# facetHound_base_module_v12.net
KiCad netlist of a schematic drawn in EAGLE
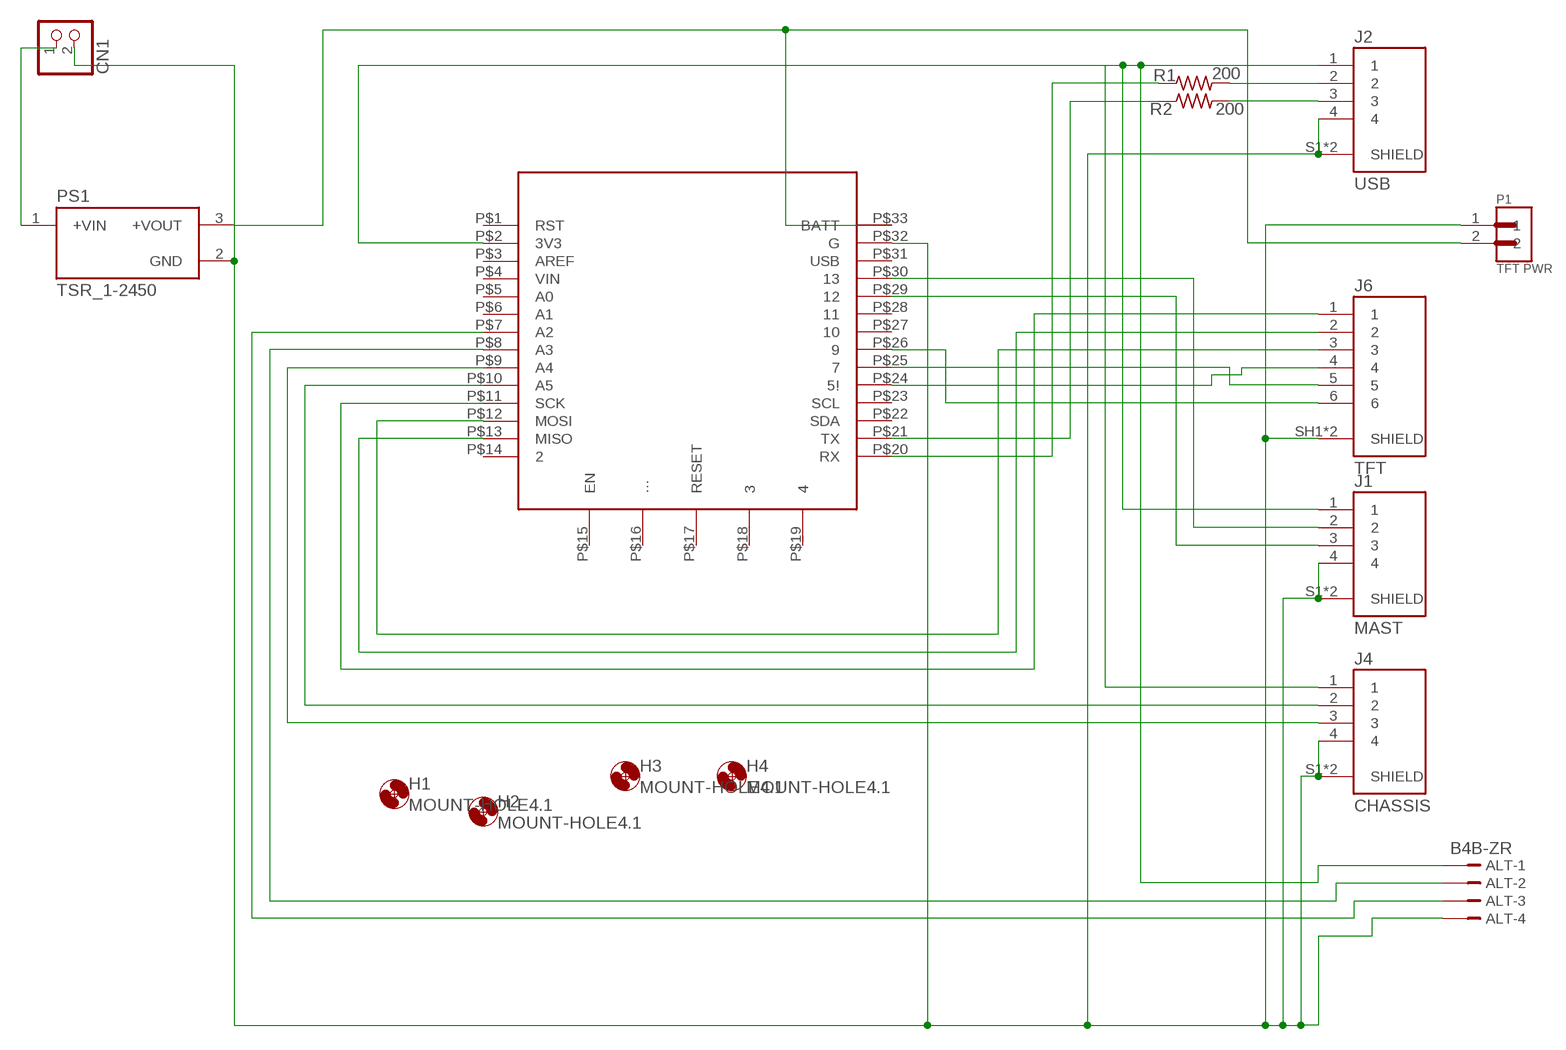
[diagram p0: schematic, sheet 1]

(export (version "E")
  (design (tool "Eeschema 10.0.6"))
  (components
    (comp (ref "ALT")
      (value "B4B-ZR")
      (footprint "eagle-import:B4B-ZR")
      (fields (field (name "MF") "FARNELL") (field (name "MPN") "B4B-ZR(LF)(SN)"))
      (libsource (lib "eagle-import") (part "?4B-ZRB"))
    )
    (comp (ref "CN1")
      (value "JST_2PIN-THM-RA")
      (footprint "eagle-import:JST-PH-2-THM-RA")
      (libsource (lib "eagle-import") (part "JST_2PIN-THM-RA"))
    )
    (comp (ref "H1")
      (value "MOUNT-HOLE4.1")
      (footprint "eagle-import:4,1")
      (libsource (lib "eagle-import") (part "MOUNT-HOLE4.1"))
    )
    (comp (ref "H2")
      (value "MOUNT-HOLE4.1")
      (footprint "eagle-import:4,1")
      (libsource (lib "eagle-import") (part "MOUNT-HOLE4.1"))
    )
    (comp (ref "H3")
      (value "MOUNT-HOLE4.1")
      (footprint "eagle-import:4,1")
      (libsource (lib "eagle-import") (part "MOUNT-HOLE4.1"))
    )
    (comp (ref "H4")
      (value "MOUNT-HOLE4.1")
      (footprint "eagle-import:4,1")
      (libsource (lib "eagle-import") (part "MOUNT-HOLE4.1"))
    )
    (comp (ref "J1")
      (value "MAST")
      (footprint "eagle-import:JST_S4B-ZR-SM4A-TF(LF)(SN)")
      (fields (field (name "MF") "JST Sales") (field (name "MP") "S4B-ZR-SM4A-TF(LF)(SN)"))
      (libsource (lib "eagle-import") (part "S4B-ZR-SM4A-TF(LF)(SN)"))
    )
    (comp (ref "J2")
      (value "USB")
      (footprint "eagle-import:JST_S4B-ZR-SM4A-TF(LF)(SN)")
      (fields (field (name "MF") "JST Sales") (field (name "MP") "S4B-ZR-SM4A-TF(LF)(SN)"))
      (libsource (lib "eagle-import") (part "S4B-ZR-SM4A-TF(LF)(SN)"))
    )
    (comp (ref "J4")
      (value "CHASSIS")
      (footprint "eagle-import:JST_S4B-ZR-SM4A-TF(LF)(SN)")
      (fields (field (name "MF") "JST Sales") (field (name "MP") "S4B-ZR-SM4A-TF(LF)(SN)"))
      (libsource (lib "eagle-import") (part "S4B-ZR-SM4A-TF(LF)(SN)"))
    )
    (comp (ref "J6")
      (value "TFT")
      (footprint "eagle-import:JST_S6B-ZR-SM4A-TF(LF)(SN)")
      (fields (field (name "MF") "JST Sales America Inc.") (field (name "MP") "S6B-ZR-SM4A-TF(LF)(SN)"))
      (libsource (lib "eagle-import") (part "S6B-ZR-SM4A-TF(LF)(SN)"))
    )
    (comp (ref "P1")
      (value "TFT PWR")
      (footprint "eagle-import:JST_S2B-ZR-SM4A-TF")
      (fields (field (name "MF") "JST Sales") (field (name "MP") "S2B-ZR-SM4A-TF"))
      (libsource (lib "eagle-import") (part "S2B-ZR-SM4A-TF"))
    )
    (comp (ref "PS1")
      (value "TSR_1-2450")
      (footprint "eagle-import:CONV_TSR_1-2450")
      (fields (field (name "MANUFACTURER") "Traco Power"))
      (libsource (lib "eagle-import") (part "TSR_1-2450"))
    )
    (comp (ref "R1")
      (value "200")
      (footprint "eagle-import:M1206")
      (libsource (lib "eagle-import") (part "R-US_M1206"))
    )
    (comp (ref "R2")
      (value "200")
      (footprint "eagle-import:M1206")
      (libsource (lib "eagle-import") (part "R-US_M1206"))
    )
    (comp (ref "U$1")
      (value "ITSYBITSY_M4")
      (footprint "eagle-import:ITSYBITSY_M4")
      (libsource (lib "eagle-import") (part "ITSYBITSY_M4"))
    )
  )
  (nets
    (net (code "1") (name "Net-(ALTB-1)") (class "Default")
      (node (ref "ALT") (pin "2") (pinfunction "1_2") (pintype "passive"))
      (node (ref "U$1") (pin "P$8") (pinfunction "A3_P$8") (pintype "bidirectional"))
    )
    (net (code "2") (name "Net-(ALTC-1)") (class "Default")
      (node (ref "ALT") (pin "3") (pinfunction "1_3") (pintype "passive"))
      (node (ref "U$1") (pin "P$7") (pinfunction "A2_P$7") (pintype "bidirectional"))
    )
    (net (code "3") (name "Net-(ALTD-1)") (class "Default")
      (node (ref "ALT") (pin "4") (pinfunction "1_4") (pintype "passive"))
      (node (ref "CN1") (pin "2") (pinfunction "1_2") (pintype "passive"))
      (node (ref "J1") (pin "4") (pinfunction "4_4") (pintype "passive"))
      (node (ref "J1") (pin "S1") (pinfunction "SHIELD_S1") (pintype "passive"))
      (node (ref "J1") (pin "S2") (pinfunction "SHIELD_S2") (pintype "passive"))
      (node (ref "J2") (pin "4") (pinfunction "4_4") (pintype "passive"))
      (node (ref "J2") (pin "S1") (pinfunction "SHIELD_S1") (pintype "passive"))
      (node (ref "J2") (pin "S2") (pinfunction "SHIELD_S2") (pintype "passive"))
      (node (ref "J4") (pin "4") (pinfunction "4_4") (pintype "passive"))
      (node (ref "J4") (pin "S1") (pinfunction "SHIELD_S1") (pintype "passive"))
      (node (ref "J4") (pin "S2") (pinfunction "SHIELD_S2") (pintype "passive"))
      (node (ref "J6") (pin "SH1") (pinfunction "SHIELD_SH1") (pintype "passive"))
      (node (ref "J6") (pin "SH2") (pinfunction "SHIELD_SH2") (pintype "passive"))
      (node (ref "P1") (pin "1") (pinfunction "1_1") (pintype "passive"))
      (node (ref "PS1") (pin "2") (pinfunction "GND_2") (pintype "power_in"))
      (node (ref "U$1") (pin "P$32") (pinfunction "G_P$32") (pintype "bidirectional"))
    )
    (net (code "4") (name "Net-(CN1-2)") (class "Default")
      (node (ref "CN1") (pin "1") (pinfunction "2_1") (pintype "passive"))
      (node (ref "PS1") (pin "1") (pinfunction "+VIN_1") (pintype "input"))
    )
    (net (code "5") (name "Net-(J2-Pad2)") (class "Default")
      (node (ref "J2") (pin "2") (pinfunction "2_2") (pintype "passive"))
      (node (ref "R1") (pin "2") (pinfunction "2_2") (pintype "passive"))
    )
    (net (code "6") (name "Net-(J2-Pad3)") (class "Default")
      (node (ref "J2") (pin "3") (pinfunction "3_3") (pintype "passive"))
      (node (ref "R2") (pin "2") (pinfunction "2_2") (pintype "passive"))
    )
    (net (code "7") (name "Net-(PS1-+VOUT)") (class "Default")
      (node (ref "P1") (pin "2") (pinfunction "2_2") (pintype "passive"))
      (node (ref "PS1") (pin "3") (pinfunction "+VOUT_3") (pintype "output"))
      (node (ref "U$1") (pin "P$33") (pinfunction "BATT_P$33") (pintype "bidirectional"))
    )
    (net (code "8") (name "Net-(U$1-3V3)") (class "Default")
      (node (ref "ALT") (pin "1") (pinfunction "1_1") (pintype "passive"))
      (node (ref "J1") (pin "1") (pinfunction "1_1") (pintype "passive"))
      (node (ref "J2") (pin "1") (pinfunction "1_1") (pintype "passive"))
      (node (ref "J4") (pin "1") (pinfunction "1_1") (pintype "passive"))
      (node (ref "U$1") (pin "P$2") (pinfunction "3V3_P$2") (pintype "bidirectional"))
    )
    (net (code "9") (name "Net-(U$1-5~{})") (class "Default")
      (node (ref "J6") (pin "4") (pinfunction "4_4") (pintype "passive"))
      (node (ref "U$1") (pin "P$24") (pinfunction "5~{}_P$24") (pintype "bidirectional"))
    )
    (net (code "10") (name "Net-(U$1-7)") (class "Default")
      (node (ref "J6") (pin "5") (pinfunction "5_5") (pintype "passive"))
      (node (ref "U$1") (pin "P$25") (pinfunction "7_P$25") (pintype "bidirectional"))
    )
    (net (code "11") (name "Net-(U$1-9)") (class "Default")
      (node (ref "J6") (pin "6") (pinfunction "6_6") (pintype "passive"))
      (node (ref "U$1") (pin "P$26") (pinfunction "9_P$26") (pintype "bidirectional"))
    )
    (net (code "12") (name "Net-(U$1-12)") (class "Default")
      (node (ref "J1") (pin "3") (pinfunction "3_3") (pintype "passive"))
      (node (ref "U$1") (pin "P$29") (pinfunction "12_P$29") (pintype "bidirectional"))
    )
    (net (code "13") (name "Net-(U$1-13)") (class "Default")
      (node (ref "J1") (pin "2") (pinfunction "2_2") (pintype "passive"))
      (node (ref "U$1") (pin "P$30") (pinfunction "13_P$30") (pintype "bidirectional"))
    )
    (net (code "14") (name "Net-(U$1-A4)") (class "Default")
      (node (ref "J4") (pin "3") (pinfunction "3_3") (pintype "passive"))
      (node (ref "U$1") (pin "P$9") (pinfunction "A4_P$9") (pintype "bidirectional"))
    )
    (net (code "15") (name "Net-(U$1-A5)") (class "Default")
      (node (ref "J4") (pin "2") (pinfunction "2_2") (pintype "passive"))
      (node (ref "U$1") (pin "P$10") (pinfunction "A5_P$10") (pintype "bidirectional"))
    )
    (net (code "16") (name "Net-(U$1-MISO)") (class "Default")
      (node (ref "J6") (pin "2") (pinfunction "2_2") (pintype "passive"))
      (node (ref "U$1") (pin "P$13") (pinfunction "MISO_P$13") (pintype "bidirectional"))
    )
    (net (code "17") (name "Net-(U$1-MOSI)") (class "Default")
      (node (ref "J6") (pin "3") (pinfunction "3_3") (pintype "passive"))
      (node (ref "U$1") (pin "P$12") (pinfunction "MOSI_P$12") (pintype "bidirectional"))
    )
    (net (code "18") (name "Net-(U$1-RX)") (class "Default")
      (node (ref "R1") (pin "1") (pinfunction "1_1") (pintype "passive"))
      (node (ref "U$1") (pin "P$20") (pinfunction "RX_P$20") (pintype "bidirectional"))
    )
    (net (code "19") (name "Net-(U$1-SCK)") (class "Default")
      (node (ref "J6") (pin "1") (pinfunction "1_1") (pintype "passive"))
      (node (ref "U$1") (pin "P$11") (pinfunction "SCK_P$11") (pintype "bidirectional"))
    )
    (net (code "20") (name "Net-(U$1-TX)") (class "Default")
      (node (ref "R2") (pin "1") (pinfunction "1_1") (pintype "passive"))
      (node (ref "U$1") (pin "P$21") (pinfunction "TX_P$21") (pintype "bidirectional"))
    )
    (net (code "21") (name "unconnected-(U$1-...-PadP$16)") (class "Default")
      (node (ref "U$1") (pin "P$16") (pinfunction "..._P$16") (pintype "bidirectional"))
    )
    (net (code "22") (name "unconnected-(U$1-2-PadP$14)") (class "Default")
      (node (ref "U$1") (pin "P$14") (pinfunction "2_P$14") (pintype "bidirectional"))
    )
    (net (code "23") (name "unconnected-(U$1-3-PadP$18)") (class "Default")
      (node (ref "U$1") (pin "P$18") (pinfunction "3_P$18") (pintype "bidirectional"))
    )
    (net (code "24") (name "unconnected-(U$1-4-PadP$19)") (class "Default")
      (node (ref "U$1") (pin "P$19") (pinfunction "4_P$19") (pintype "bidirectional"))
    )
    (net (code "25") (name "unconnected-(U$1-10-PadP$27)") (class "Default")
      (node (ref "U$1") (pin "P$27") (pinfunction "10_P$27") (pintype "bidirectional"))
    )
    (net (code "26") (name "unconnected-(U$1-11-PadP$28)") (class "Default")
      (node (ref "U$1") (pin "P$28") (pinfunction "11_P$28") (pintype "bidirectional"))
    )
    (net (code "27") (name "unconnected-(U$1-A0-PadP$5)") (class "Default")
      (node (ref "U$1") (pin "P$5") (pinfunction "A0_P$5") (pintype "bidirectional"))
    )
    (net (code "28") (name "unconnected-(U$1-A1-PadP$6)") (class "Default")
      (node (ref "U$1") (pin "P$6") (pinfunction "A1_P$6") (pintype "bidirectional"))
    )
    (net (code "29") (name "unconnected-(U$1-AREF-PadP$3)") (class "Default")
      (node (ref "U$1") (pin "P$3") (pinfunction "AREF_P$3") (pintype "bidirectional"))
    )
    (net (code "30") (name "unconnected-(U$1-EN-PadP$15)") (class "Default")
      (node (ref "U$1") (pin "P$15") (pinfunction "EN_P$15") (pintype "bidirectional"))
    )
    (net (code "31") (name "unconnected-(U$1-RESET-PadP$17)") (class "Default")
      (node (ref "U$1") (pin "P$17") (pinfunction "RESET_P$17") (pintype "bidirectional"))
    )
    (net (code "32") (name "unconnected-(U$1-RST-PadP$1)") (class "Default")
      (node (ref "U$1") (pin "P$1") (pinfunction "RST_P$1") (pintype "bidirectional"))
    )
    (net (code "33") (name "unconnected-(U$1-SCL-PadP$23)") (class "Default")
      (node (ref "U$1") (pin "P$23") (pinfunction "SCL_P$23") (pintype "bidirectional"))
    )
    (net (code "34") (name "unconnected-(U$1-SDA-PadP$22)") (class "Default")
      (node (ref "U$1") (pin "P$22") (pinfunction "SDA_P$22") (pintype "bidirectional"))
    )
    (net (code "35") (name "unconnected-(U$1-USB-PadP$31)") (class "Default")
      (node (ref "U$1") (pin "P$31") (pinfunction "USB_P$31") (pintype "bidirectional"))
    )
    (net (code "36") (name "unconnected-(U$1-VIN-PadP$4)") (class "Default")
      (node (ref "U$1") (pin "P$4") (pinfunction "VIN_P$4") (pintype "bidirectional"))
    )
  )
)
